# CW342_FPGIO_2.net
KiCad netlist of a schematic drawn in Altium Designer
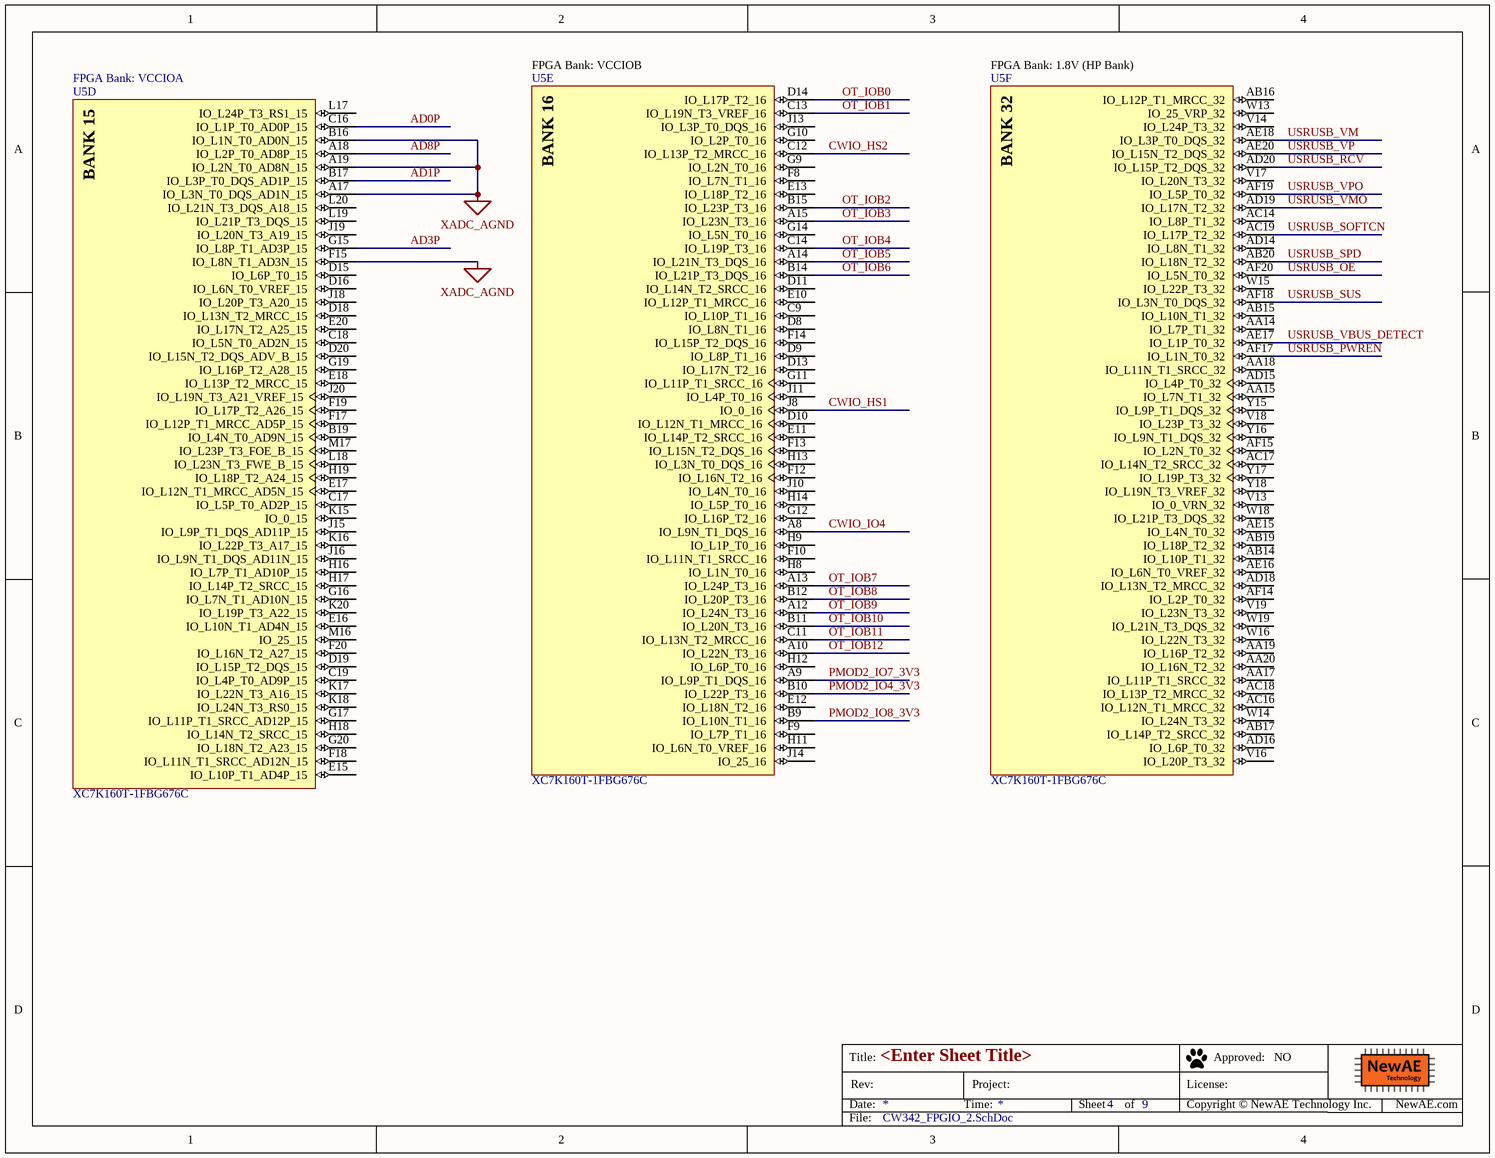
[diagram p0: CW342_FPGIO_2.SchDoc]

(export (version "E")
  (design (tool "Eeschema 10.0.6"))
  (components
    (comp (ref "U5")
      (value "XC7K160T-1FBG676C")
      (footprint "FBG676")
      (description "Kintex-7 FPGA, 400 User I/Os, 8 GTX, 676-Ball BGA, Speed Grade 1, Commercial Grade, Pb-Free")
      (fields (field (name "GENERIC PART NUMBER") "XC7K160T") (field (name "MANUFACTURER") "Xilinx"))
      (libsource (lib "") (part "XNLX-XC7K160T-XNLX-FBG676_1"))
    )
  )
  (nets
    (net (code "1") (name "/AD0P") (class "Default")
      (node (ref "U5") (pin "C16") (pinfunction "IO_L1P_T0_AD0P_15_C16") (pintype "bidirectional"))
    )
    (net (code "2") (name "/AD1P") (class "Default")
      (node (ref "U5") (pin "B17") (pinfunction "IO_L3P_T0_DQS_AD1P_15_B17") (pintype "bidirectional"))
    )
    (net (code "3") (name "/AD3P") (class "Default")
      (node (ref "U5") (pin "G15") (pinfunction "IO_L8P_T1_AD3P_15_G15") (pintype "bidirectional"))
    )
    (net (code "4") (name "/AD8P") (class "Default")
      (node (ref "U5") (pin "A18") (pinfunction "IO_L2P_T0_AD8P_15_A18") (pintype "bidirectional"))
    )
    (net (code "5") (name "/CWIO_HS1") (class "Default")
      (node (ref "U5") (pin "J8") (pinfunction "IO_0_16_J8") (pintype "bidirectional"))
    )
    (net (code "6") (name "/CWIO_HS2") (class "Default")
      (node (ref "U5") (pin "C12") (pinfunction "IO_L13P_T2_MRCC_16_C12") (pintype "bidirectional"))
    )
    (net (code "7") (name "/CWIO_IO4") (class "Default")
      (node (ref "U5") (pin "A8") (pinfunction "IO_L9N_T1_DQS_16_A8") (pintype "bidirectional"))
    )
    (net (code "8") (name "/OT_IOB0") (class "Default")
      (node (ref "U5") (pin "D14") (pinfunction "IO_L17P_T2_16_D14") (pintype "bidirectional"))
    )
    (net (code "9") (name "/OT_IOB1") (class "Default")
      (node (ref "U5") (pin "C13") (pinfunction "IO_L19N_T3_VREF_16_C13") (pintype "bidirectional"))
    )
    (net (code "10") (name "/OT_IOB2") (class "Default")
      (node (ref "U5") (pin "B15") (pinfunction "IO_L23P_T3_16_B15") (pintype "bidirectional"))
    )
    (net (code "11") (name "/OT_IOB3") (class "Default")
      (node (ref "U5") (pin "A15") (pinfunction "IO_L23N_T3_16_A15") (pintype "bidirectional"))
    )
    (net (code "12") (name "/OT_IOB4") (class "Default")
      (node (ref "U5") (pin "C14") (pinfunction "IO_L19P_T3_16_C14") (pintype "bidirectional"))
    )
    (net (code "13") (name "/OT_IOB5") (class "Default")
      (node (ref "U5") (pin "A14") (pinfunction "IO_L21N_T3_DQS_16_A14") (pintype "bidirectional"))
    )
    (net (code "14") (name "/OT_IOB6") (class "Default")
      (node (ref "U5") (pin "B14") (pinfunction "IO_L21P_T3_DQS_16_B14") (pintype "bidirectional"))
    )
    (net (code "15") (name "/OT_IOB7") (class "Default")
      (node (ref "U5") (pin "A13") (pinfunction "IO_L24P_T3_16_A13") (pintype "bidirectional"))
    )
    (net (code "16") (name "/OT_IOB8") (class "Default")
      (node (ref "U5") (pin "B12") (pinfunction "IO_L20P_T3_16_B12") (pintype "bidirectional"))
    )
    (net (code "17") (name "/OT_IOB9") (class "Default")
      (node (ref "U5") (pin "A12") (pinfunction "IO_L24N_T3_16_A12") (pintype "bidirectional"))
    )
    (net (code "18") (name "/OT_IOB10") (class "Default")
      (node (ref "U5") (pin "B11") (pinfunction "IO_L20N_T3_16_B11") (pintype "bidirectional"))
    )
    (net (code "19") (name "/OT_IOB11") (class "Default")
      (node (ref "U5") (pin "C11") (pinfunction "IO_L13N_T2_MRCC_16_C11") (pintype "bidirectional"))
    )
    (net (code "20") (name "/OT_IOB12") (class "Default")
      (node (ref "U5") (pin "A10") (pinfunction "IO_L22N_T3_16_A10") (pintype "bidirectional"))
    )
    (net (code "21") (name "/PMOD2_IO4_3V3") (class "Default")
      (node (ref "U5") (pin "B10") (pinfunction "IO_L22P_T3_16_B10") (pintype "bidirectional"))
    )
    (net (code "22") (name "/PMOD2_IO7_3V3") (class "Default")
      (node (ref "U5") (pin "A9") (pinfunction "IO_L9P_T1_DQS_16_A9") (pintype "bidirectional"))
    )
    (net (code "23") (name "/PMOD2_IO8_3V3") (class "Default")
      (node (ref "U5") (pin "B9") (pinfunction "IO_L10N_T1_16_B9") (pintype "bidirectional"))
    )
    (net (code "24") (name "/USRUSB_OE") (class "Default")
      (node (ref "U5") (pin "AF20") (pinfunction "IO_L5N_T0_32_AF20") (pintype "bidirectional"))
    )
    (net (code "25") (name "/USRUSB_PWREN") (class "Default")
      (node (ref "U5") (pin "AF17") (pinfunction "IO_L1N_T0_32_AF17") (pintype "bidirectional"))
    )
    (net (code "26") (name "/USRUSB_RCV") (class "Default")
      (node (ref "U5") (pin "AD20") (pinfunction "IO_L15P_T2_DQS_32_AD20") (pintype "bidirectional"))
    )
    (net (code "27") (name "/USRUSB_SOFTCN") (class "Default")
      (node (ref "U5") (pin "AC19") (pinfunction "IO_L17P_T2_32_AC19") (pintype "bidirectional"))
    )
    (net (code "28") (name "/USRUSB_SPD") (class "Default")
      (node (ref "U5") (pin "AB20") (pinfunction "IO_L18N_T2_32_AB20") (pintype "bidirectional"))
    )
    (net (code "29") (name "/USRUSB_SUS") (class "Default")
      (node (ref "U5") (pin "AF18") (pinfunction "IO_L3N_T0_DQS_32_AF18") (pintype "bidirectional"))
    )
    (net (code "30") (name "/USRUSB_VBUS_DETECT") (class "Default")
      (node (ref "U5") (pin "AE17") (pinfunction "IO_L1P_T0_32_AE17") (pintype "bidirectional"))
    )
    (net (code "31") (name "/USRUSB_VM") (class "Default")
      (node (ref "U5") (pin "AE18") (pinfunction "IO_L3P_T0_DQS_32_AE18") (pintype "bidirectional"))
    )
    (net (code "32") (name "/USRUSB_VMO") (class "Default")
      (node (ref "U5") (pin "AD19") (pinfunction "IO_L17N_T2_32_AD19") (pintype "bidirectional"))
    )
    (net (code "33") (name "/USRUSB_VP") (class "Default")
      (node (ref "U5") (pin "AE20") (pinfunction "IO_L15N_T2_DQS_32_AE20") (pintype "bidirectional"))
    )
    (net (code "34") (name "/USRUSB_VPO") (class "Default")
      (node (ref "U5") (pin "AF19") (pinfunction "IO_L5P_T0_32_AF19") (pintype "bidirectional"))
    )
    (net (code "35") (name "XADC_AGND") (class "Default")
      (node (ref "U5") (pin "A17") (pinfunction "IO_L3N_T0_DQS_AD1N_15_A17") (pintype "bidirectional"))
      (node (ref "U5") (pin "A19") (pinfunction "IO_L2N_T0_AD8N_15_A19") (pintype "bidirectional"))
      (node (ref "U5") (pin "B16") (pinfunction "IO_L1N_T0_AD0N_15_B16") (pintype "bidirectional"))
      (node (ref "U5") (pin "F15") (pinfunction "IO_L8N_T1_AD3N_15_F15") (pintype "bidirectional"))
    )
    (net (code "36") (name "unconnected-(U5D-IO_0_15-PadK15)") (class "Default")
      (node (ref "U5") (pin "K15") (pinfunction "IO_0_15_K15") (pintype "bidirectional"))
    )
    (net (code "37") (name "unconnected-(U5D-IO_25_15-PadM16)") (class "Default")
      (node (ref "U5") (pin "M16") (pinfunction "IO_25_15_M16") (pintype "bidirectional"))
    )
    (net (code "38") (name "unconnected-(U5D-IO_L4N_T0_AD9N_15-PadB19)") (class "Default")
      (node (ref "U5") (pin "B19") (pinfunction "IO_L4N_T0_AD9N_15_B19") (pintype "bidirectional"))
    )
    (net (code "39") (name "unconnected-(U5D-IO_L4P_T0_AD9P_15-PadC19)") (class "Default")
      (node (ref "U5") (pin "C19") (pinfunction "IO_L4P_T0_AD9P_15_C19") (pintype "bidirectional"))
    )
    (net (code "40") (name "unconnected-(U5D-IO_L5N_T0_AD2N_15-PadC18)") (class "Default")
      (node (ref "U5") (pin "C18") (pinfunction "IO_L5N_T0_AD2N_15_C18") (pintype "bidirectional"))
    )
    (net (code "41") (name "unconnected-(U5D-IO_L5P_T0_AD2P_15-PadC17)") (class "Default")
      (node (ref "U5") (pin "C17") (pinfunction "IO_L5P_T0_AD2P_15_C17") (pintype "bidirectional"))
    )
    (net (code "42") (name "unconnected-(U5D-IO_L6N_T0_VREF_15-PadD16)") (class "Default")
      (node (ref "U5") (pin "D16") (pinfunction "IO_L6N_T0_VREF_15_D16") (pintype "bidirectional"))
    )
    (net (code "43") (name "unconnected-(U5D-IO_L6P_T0_15-PadD15)") (class "Default")
      (node (ref "U5") (pin "D15") (pinfunction "IO_L6P_T0_15_D15") (pintype "bidirectional"))
    )
    (net (code "44") (name "unconnected-(U5D-IO_L7N_T1_AD10N_15-PadG16)") (class "Default")
      (node (ref "U5") (pin "G16") (pinfunction "IO_L7N_T1_AD10N_15_G16") (pintype "bidirectional"))
    )
    (net (code "45") (name "unconnected-(U5D-IO_L7P_T1_AD10P_15-PadH16)") (class "Default")
      (node (ref "U5") (pin "H16") (pinfunction "IO_L7P_T1_AD10P_15_H16") (pintype "bidirectional"))
    )
    (net (code "46") (name "unconnected-(U5D-IO_L9N_T1_DQS_AD11N_15-PadJ16)") (class "Default")
      (node (ref "U5") (pin "J16") (pinfunction "IO_L9N_T1_DQS_AD11N_15_J16") (pintype "bidirectional"))
    )
    (net (code "47") (name "unconnected-(U5D-IO_L9P_T1_DQS_AD11P_15-PadJ15)") (class "Default")
      (node (ref "U5") (pin "J15") (pinfunction "IO_L9P_T1_DQS_AD11P_15_J15") (pintype "bidirectional"))
    )
    (net (code "48") (name "unconnected-(U5D-IO_L10N_T1_AD4N_15-PadE16)") (class "Default")
      (node (ref "U5") (pin "E16") (pinfunction "IO_L10N_T1_AD4N_15_E16") (pintype "bidirectional"))
    )
    (net (code "49") (name "unconnected-(U5D-IO_L10P_T1_AD4P_15-PadE15)") (class "Default")
      (node (ref "U5") (pin "E15") (pinfunction "IO_L10P_T1_AD4P_15_E15") (pintype "bidirectional"))
    )
    (net (code "50") (name "unconnected-(U5D-IO_L11N_T1_SRCC_AD12N_15-PadF18)") (class "Default")
      (node (ref "U5") (pin "F18") (pinfunction "IO_L11N_T1_SRCC_AD12N_15_F18") (pintype "bidirectional"))
    )
    (net (code "51") (name "unconnected-(U5D-IO_L11P_T1_SRCC_AD12P_15-PadG17)") (class "Default")
      (node (ref "U5") (pin "G17") (pinfunction "IO_L11P_T1_SRCC_AD12P_15_G17") (pintype "bidirectional"))
    )
    (net (code "52") (name "unconnected-(U5D-IO_L12N_T1_MRCC_AD5N_15-PadE17)") (class "Default")
      (node (ref "U5") (pin "E17") (pinfunction "IO_L12N_T1_MRCC_AD5N_15_E17") (pintype "bidirectional"))
    )
    (net (code "53") (name "unconnected-(U5D-IO_L12P_T1_MRCC_AD5P_15-PadF17)") (class "Default")
      (node (ref "U5") (pin "F17") (pinfunction "IO_L12P_T1_MRCC_AD5P_15_F17") (pintype "bidirectional"))
    )
    (net (code "54") (name "unconnected-(U5D-IO_L13N_T2_MRCC_15-PadD18)") (class "Default")
      (node (ref "U5") (pin "D18") (pinfunction "IO_L13N_T2_MRCC_15_D18") (pintype "bidirectional"))
    )
    (net (code "55") (name "unconnected-(U5D-IO_L13P_T2_MRCC_15-PadE18)") (class "Default")
      (node (ref "U5") (pin "E18") (pinfunction "IO_L13P_T2_MRCC_15_E18") (pintype "bidirectional"))
    )
    (net (code "56") (name "unconnected-(U5D-IO_L14N_T2_SRCC_15-PadH18)") (class "Default")
      (node (ref "U5") (pin "H18") (pinfunction "IO_L14N_T2_SRCC_15_H18") (pintype "bidirectional"))
    )
    (net (code "57") (name "unconnected-(U5D-IO_L14P_T2_SRCC_15-PadH17)") (class "Default")
      (node (ref "U5") (pin "H17") (pinfunction "IO_L14P_T2_SRCC_15_H17") (pintype "bidirectional"))
    )
    (net (code "58") (name "unconnected-(U5D-IO_L15N_T2_DQS_ADV_B_15-PadD20)") (class "Default")
      (node (ref "U5") (pin "D20") (pinfunction "IO_L15N_T2_DQS_ADV_B_15_D20") (pintype "bidirectional"))
    )
    (net (code "59") (name "unconnected-(U5D-IO_L15P_T2_DQS_15-PadD19)") (class "Default")
      (node (ref "U5") (pin "D19") (pinfunction "IO_L15P_T2_DQS_15_D19") (pintype "bidirectional"))
    )
    (net (code "60") (name "unconnected-(U5D-IO_L16N_T2_A27_15-PadF20)") (class "Default")
      (node (ref "U5") (pin "F20") (pinfunction "IO_L16N_T2_A27_15_F20") (pintype "bidirectional"))
    )
    (net (code "61") (name "unconnected-(U5D-IO_L16P_T2_A28_15-PadG19)") (class "Default")
      (node (ref "U5") (pin "G19") (pinfunction "IO_L16P_T2_A28_15_G19") (pintype "bidirectional"))
    )
    (net (code "62") (name "unconnected-(U5D-IO_L17N_T2_A25_15-PadE20)") (class "Default")
      (node (ref "U5") (pin "E20") (pinfunction "IO_L17N_T2_A25_15_E20") (pintype "bidirectional"))
    )
    (net (code "63") (name "unconnected-(U5D-IO_L17P_T2_A26_15-PadF19)") (class "Default")
      (node (ref "U5") (pin "F19") (pinfunction "IO_L17P_T2_A26_15_F19") (pintype "bidirectional"))
    )
    (net (code "64") (name "unconnected-(U5D-IO_L18N_T2_A23_15-PadG20)") (class "Default")
      (node (ref "U5") (pin "G20") (pinfunction "IO_L18N_T2_A23_15_G20") (pintype "bidirectional"))
    )
    (net (code "65") (name "unconnected-(U5D-IO_L18P_T2_A24_15-PadH19)") (class "Default")
      (node (ref "U5") (pin "H19") (pinfunction "IO_L18P_T2_A24_15_H19") (pintype "bidirectional"))
    )
    (net (code "66") (name "unconnected-(U5D-IO_L19N_T3_A21_VREF_15-PadJ20)") (class "Default")
      (node (ref "U5") (pin "J20") (pinfunction "IO_L19N_T3_A21_VREF_15_J20") (pintype "bidirectional"))
    )
    (net (code "67") (name "unconnected-(U5D-IO_L19P_T3_A22_15-PadK20)") (class "Default")
      (node (ref "U5") (pin "K20") (pinfunction "IO_L19P_T3_A22_15_K20") (pintype "bidirectional"))
    )
    (net (code "68") (name "unconnected-(U5D-IO_L20N_T3_A19_15-PadJ19)") (class "Default")
      (node (ref "U5") (pin "J19") (pinfunction "IO_L20N_T3_A19_15_J19") (pintype "bidirectional"))
    )
    (net (code "69") (name "unconnected-(U5D-IO_L20P_T3_A20_15-PadJ18)") (class "Default")
      (node (ref "U5") (pin "J18") (pinfunction "IO_L20P_T3_A20_15_J18") (pintype "bidirectional"))
    )
    (net (code "70") (name "unconnected-(U5D-IO_L21N_T3_DQS_A18_15-PadL20)") (class "Default")
      (node (ref "U5") (pin "L20") (pinfunction "IO_L21N_T3_DQS_A18_15_L20") (pintype "bidirectional"))
    )
    (net (code "71") (name "unconnected-(U5D-IO_L21P_T3_DQS_15-PadL19)") (class "Default")
      (node (ref "U5") (pin "L19") (pinfunction "IO_L21P_T3_DQS_15_L19") (pintype "bidirectional"))
    )
    (net (code "72") (name "unconnected-(U5D-IO_L22N_T3_A16_15-PadK17)") (class "Default")
      (node (ref "U5") (pin "K17") (pinfunction "IO_L22N_T3_A16_15_K17") (pintype "bidirectional"))
    )
    (net (code "73") (name "unconnected-(U5D-IO_L22P_T3_A17_15-PadK16)") (class "Default")
      (node (ref "U5") (pin "K16") (pinfunction "IO_L22P_T3_A17_15_K16") (pintype "bidirectional"))
    )
    (net (code "74") (name "unconnected-(U5D-IO_L23N_T3_FWE_B_15-PadL18)") (class "Default")
      (node (ref "U5") (pin "L18") (pinfunction "IO_L23N_T3_FWE_B_15_L18") (pintype "bidirectional"))
    )
    (net (code "75") (name "unconnected-(U5D-IO_L23P_T3_FOE_B_15-PadM17)") (class "Default")
      (node (ref "U5") (pin "M17") (pinfunction "IO_L23P_T3_FOE_B_15_M17") (pintype "bidirectional"))
    )
    (net (code "76") (name "unconnected-(U5D-IO_L24N_T3_RS0_15-PadK18)") (class "Default")
      (node (ref "U5") (pin "K18") (pinfunction "IO_L24N_T3_RS0_15_K18") (pintype "bidirectional"))
    )
    (net (code "77") (name "unconnected-(U5D-IO_L24P_T3_RS1_15-PadL17)") (class "Default")
      (node (ref "U5") (pin "L17") (pinfunction "IO_L24P_T3_RS1_15_L17") (pintype "bidirectional"))
    )
    (net (code "78") (name "unconnected-(U5E-IO_25_16-PadJ14)") (class "Default")
      (node (ref "U5") (pin "J14") (pinfunction "IO_25_16_J14") (pintype "bidirectional"))
    )
    (net (code "79") (name "unconnected-(U5E-IO_L1N_T0_16-PadH8)") (class "Default")
      (node (ref "U5") (pin "H8") (pinfunction "IO_L1N_T0_16_H8") (pintype "bidirectional"))
    )
    (net (code "80") (name "unconnected-(U5E-IO_L1P_T0_16-PadH9)") (class "Default")
      (node (ref "U5") (pin "H9") (pinfunction "IO_L1P_T0_16_H9") (pintype "bidirectional"))
    )
    (net (code "81") (name "unconnected-(U5E-IO_L2N_T0_16-PadG9)") (class "Default")
      (node (ref "U5") (pin "G9") (pinfunction "IO_L2N_T0_16_G9") (pintype "bidirectional"))
    )
    (net (code "82") (name "unconnected-(U5E-IO_L2P_T0_16-PadG10)") (class "Default")
      (node (ref "U5") (pin "G10") (pinfunction "IO_L2P_T0_16_G10") (pintype "bidirectional"))
    )
    (net (code "83") (name "unconnected-(U5E-IO_L3N_T0_DQS_16-PadH13)") (class "Default")
      (node (ref "U5") (pin "H13") (pinfunction "IO_L3N_T0_DQS_16_H13") (pintype "bidirectional"))
    )
    (net (code "84") (name "unconnected-(U5E-IO_L3P_T0_DQS_16-PadJ13)") (class "Default")
      (node (ref "U5") (pin "J13") (pinfunction "IO_L3P_T0_DQS_16_J13") (pintype "bidirectional"))
    )
    (net (code "85") (name "unconnected-(U5E-IO_L4N_T0_16-PadJ10)") (class "Default")
      (node (ref "U5") (pin "J10") (pinfunction "IO_L4N_T0_16_J10") (pintype "bidirectional"))
    )
    (net (code "86") (name "unconnected-(U5E-IO_L4P_T0_16-PadJ11)") (class "Default")
      (node (ref "U5") (pin "J11") (pinfunction "IO_L4P_T0_16_J11") (pintype "bidirectional"))
    )
    (net (code "87") (name "unconnected-(U5E-IO_L5N_T0_16-PadG14)") (class "Default")
      (node (ref "U5") (pin "G14") (pinfunction "IO_L5N_T0_16_G14") (pintype "bidirectional"))
    )
    (net (code "88") (name "unconnected-(U5E-IO_L5P_T0_16-PadH14)") (class "Default")
      (node (ref "U5") (pin "H14") (pinfunction "IO_L5P_T0_16_H14") (pintype "bidirectional"))
    )
    (net (code "89") (name "unconnected-(U5E-IO_L6N_T0_VREF_16-PadH11)") (class "Default")
      (node (ref "U5") (pin "H11") (pinfunction "IO_L6N_T0_VREF_16_H11") (pintype "bidirectional"))
    )
    (net (code "90") (name "unconnected-(U5E-IO_L6P_T0_16-PadH12)") (class "Default")
      (node (ref "U5") (pin "H12") (pinfunction "IO_L6P_T0_16_H12") (pintype "bidirectional"))
    )
    (net (code "91") (name "unconnected-(U5E-IO_L7N_T1_16-PadF8)") (class "Default")
      (node (ref "U5") (pin "F8") (pinfunction "IO_L7N_T1_16_F8") (pintype "bidirectional"))
    )
    (net (code "92") (name "unconnected-(U5E-IO_L7P_T1_16-PadF9)") (class "Default")
      (node (ref "U5") (pin "F9") (pinfunction "IO_L7P_T1_16_F9") (pintype "bidirectional"))
    )
    (net (code "93") (name "unconnected-(U5E-IO_L8N_T1_16-PadD8)") (class "Default")
      (node (ref "U5") (pin "D8") (pinfunction "IO_L8N_T1_16_D8") (pintype "bidirectional"))
    )
    (net (code "94") (name "unconnected-(U5E-IO_L8P_T1_16-PadD9)") (class "Default")
      (node (ref "U5") (pin "D9") (pinfunction "IO_L8P_T1_16_D9") (pintype "bidirectional"))
    )
    (net (code "95") (name "unconnected-(U5E-IO_L10P_T1_16-PadC9)") (class "Default")
      (node (ref "U5") (pin "C9") (pinfunction "IO_L10P_T1_16_C9") (pintype "bidirectional"))
    )
    (net (code "96") (name "unconnected-(U5E-IO_L11N_T1_SRCC_16-PadF10)") (class "Default")
      (node (ref "U5") (pin "F10") (pinfunction "IO_L11N_T1_SRCC_16_F10") (pintype "bidirectional"))
    )
    (net (code "97") (name "unconnected-(U5E-IO_L11P_T1_SRCC_16-PadG11)") (class "Default")
      (node (ref "U5") (pin "G11") (pinfunction "IO_L11P_T1_SRCC_16_G11") (pintype "bidirectional"))
    )
    (net (code "98") (name "unconnected-(U5E-IO_L12N_T1_MRCC_16-PadD10)") (class "Default")
      (node (ref "U5") (pin "D10") (pinfunction "IO_L12N_T1_MRCC_16_D10") (pintype "bidirectional"))
    )
    (net (code "99") (name "unconnected-(U5E-IO_L12P_T1_MRCC_16-PadE10)") (class "Default")
      (node (ref "U5") (pin "E10") (pinfunction "IO_L12P_T1_MRCC_16_E10") (pintype "bidirectional"))
    )
    (net (code "100") (name "unconnected-(U5E-IO_L14N_T2_SRCC_16-PadD11)") (class "Default")
      (node (ref "U5") (pin "D11") (pinfunction "IO_L14N_T2_SRCC_16_D11") (pintype "bidirectional"))
    )
    (net (code "101") (name "unconnected-(U5E-IO_L14P_T2_SRCC_16-PadE11)") (class "Default")
      (node (ref "U5") (pin "E11") (pinfunction "IO_L14P_T2_SRCC_16_E11") (pintype "bidirectional"))
    )
    (net (code "102") (name "unconnected-(U5E-IO_L15N_T2_DQS_16-PadF13)") (class "Default")
      (node (ref "U5") (pin "F13") (pinfunction "IO_L15N_T2_DQS_16_F13") (pintype "bidirectional"))
    )
    (net (code "103") (name "unconnected-(U5E-IO_L15P_T2_DQS_16-PadF14)") (class "Default")
      (node (ref "U5") (pin "F14") (pinfunction "IO_L15P_T2_DQS_16_F14") (pintype "bidirectional"))
    )
    (net (code "104") (name "unconnected-(U5E-IO_L16N_T2_16-PadF12)") (class "Default")
      (node (ref "U5") (pin "F12") (pinfunction "IO_L16N_T2_16_F12") (pintype "bidirectional"))
    )
    (net (code "105") (name "unconnected-(U5E-IO_L16P_T2_16-PadG12)") (class "Default")
      (node (ref "U5") (pin "G12") (pinfunction "IO_L16P_T2_16_G12") (pintype "bidirectional"))
    )
    (net (code "106") (name "unconnected-(U5E-IO_L17N_T2_16-PadD13)") (class "Default")
      (node (ref "U5") (pin "D13") (pinfunction "IO_L17N_T2_16_D13") (pintype "bidirectional"))
    )
    (net (code "107") (name "unconnected-(U5E-IO_L18N_T2_16-PadE12)") (class "Default")
      (node (ref "U5") (pin "E12") (pinfunction "IO_L18N_T2_16_E12") (pintype "bidirectional"))
    )
    (net (code "108") (name "unconnected-(U5E-IO_L18P_T2_16-PadE13)") (class "Default")
      (node (ref "U5") (pin "E13") (pinfunction "IO_L18P_T2_16_E13") (pintype "bidirectional"))
    )
    (net (code "109") (name "unconnected-(U5F-IO_0_VRN_32-PadV13)") (class "Default")
      (node (ref "U5") (pin "V13") (pinfunction "IO_0_VRN_32_V13") (pintype "bidirectional"))
    )
    (net (code "110") (name "unconnected-(U5F-IO_25_VRP_32-PadW13)") (class "Default")
      (node (ref "U5") (pin "W13") (pinfunction "IO_25_VRP_32_W13") (pintype "bidirectional"))
    )
    (net (code "111") (name "unconnected-(U5F-IO_L2N_T0_32-PadAF15)") (class "Default")
      (node (ref "U5") (pin "AF15") (pinfunction "IO_L2N_T0_32_AF15") (pintype "bidirectional"))
    )
    (net (code "112") (name "unconnected-(U5F-IO_L2P_T0_32-PadAF14)") (class "Default")
      (node (ref "U5") (pin "AF14") (pinfunction "IO_L2P_T0_32_AF14") (pintype "bidirectional"))
    )
    (net (code "113") (name "unconnected-(U5F-IO_L4N_T0_32-PadAE15)") (class "Default")
      (node (ref "U5") (pin "AE15") (pinfunction "IO_L4N_T0_32_AE15") (pintype "bidirectional"))
    )
    (net (code "114") (name "unconnected-(U5F-IO_L4P_T0_32-PadAD15)") (class "Default")
      (node (ref "U5") (pin "AD15") (pinfunction "IO_L4P_T0_32_AD15") (pintype "bidirectional"))
    )
    (net (code "115") (name "unconnected-(U5F-IO_L6N_T0_VREF_32-PadAE16)") (class "Default")
      (node (ref "U5") (pin "AE16") (pinfunction "IO_L6N_T0_VREF_32_AE16") (pintype "bidirectional"))
    )
    (net (code "116") (name "unconnected-(U5F-IO_L6P_T0_32-PadAD16)") (class "Default")
      (node (ref "U5") (pin "AD16") (pinfunction "IO_L6P_T0_32_AD16") (pintype "bidirectional"))
    )
    (net (code "117") (name "unconnected-(U5F-IO_L7N_T1_32-PadAA15)") (class "Default")
      (node (ref "U5") (pin "AA15") (pinfunction "IO_L7N_T1_32_AA15") (pintype "bidirectional"))
    )
    (net (code "118") (name "unconnected-(U5F-IO_L7P_T1_32-PadAA14)") (class "Default")
      (node (ref "U5") (pin "AA14") (pinfunction "IO_L7P_T1_32_AA14") (pintype "bidirectional"))
    )
    (net (code "119") (name "unconnected-(U5F-IO_L8N_T1_32-PadAD14)") (class "Default")
      (node (ref "U5") (pin "AD14") (pinfunction "IO_L8N_T1_32_AD14") (pintype "bidirectional"))
    )
    (net (code "120") (name "unconnected-(U5F-IO_L8P_T1_32-PadAC14)") (class "Default")
      (node (ref "U5") (pin "AC14") (pinfunction "IO_L8P_T1_32_AC14") (pintype "bidirectional"))
    )
    (net (code "121") (name "unconnected-(U5F-IO_L9N_T1_DQS_32-PadY16)") (class "Default")
      (node (ref "U5") (pin "Y16") (pinfunction "IO_L9N_T1_DQS_32_Y16") (pintype "bidirectional"))
    )
    (net (code "122") (name "unconnected-(U5F-IO_L9P_T1_DQS_32-PadY15)") (class "Default")
      (node (ref "U5") (pin "Y15") (pinfunction "IO_L9P_T1_DQS_32_Y15") (pintype "bidirectional"))
    )
    (net (code "123") (name "unconnected-(U5F-IO_L10N_T1_32-PadAB15)") (class "Default")
      (node (ref "U5") (pin "AB15") (pinfunction "IO_L10N_T1_32_AB15") (pintype "bidirectional"))
    )
    (net (code "124") (name "unconnected-(U5F-IO_L10P_T1_32-PadAB14)") (class "Default")
      (node (ref "U5") (pin "AB14") (pinfunction "IO_L10P_T1_32_AB14") (pintype "bidirectional"))
    )
    (net (code "125") (name "unconnected-(U5F-IO_L11N_T1_SRCC_32-PadAA18)") (class "Default")
      (node (ref "U5") (pin "AA18") (pinfunction "IO_L11N_T1_SRCC_32_AA18") (pintype "bidirectional"))
    )
    (net (code "126") (name "unconnected-(U5F-IO_L11P_T1_SRCC_32-PadAA17)") (class "Default")
      (node (ref "U5") (pin "AA17") (pinfunction "IO_L11P_T1_SRCC_32_AA17") (pintype "bidirectional"))
    )
    (net (code "127") (name "unconnected-(U5F-IO_L12N_T1_MRCC_32-PadAC16)") (class "Default")
      (node (ref "U5") (pin "AC16") (pinfunction "IO_L12N_T1_MRCC_32_AC16") (pintype "bidirectional"))
    )
    (net (code "128") (name "unconnected-(U5F-IO_L12P_T1_MRCC_32-PadAB16)") (class "Default")
      (node (ref "U5") (pin "AB16") (pinfunction "IO_L12P_T1_MRCC_32_AB16") (pintype "bidirectional"))
    )
    (net (code "129") (name "unconnected-(U5F-IO_L13N_T2_MRCC_32-PadAD18)") (class "Default")
      (node (ref "U5") (pin "AD18") (pinfunction "IO_L13N_T2_MRCC_32_AD18") (pintype "bidirectional"))
    )
    (net (code "130") (name "unconnected-(U5F-IO_L13P_T2_MRCC_32-PadAC18)") (class "Default")
      (node (ref "U5") (pin "AC18") (pinfunction "IO_L13P_T2_MRCC_32_AC18") (pintype "bidirectional"))
    )
    (net (code "131") (name "unconnected-(U5F-IO_L14N_T2_SRCC_32-PadAC17)") (class "Default")
      (node (ref "U5") (pin "AC17") (pinfunction "IO_L14N_T2_SRCC_32_AC17") (pintype "bidirectional"))
    )
    (net (code "132") (name "unconnected-(U5F-IO_L14P_T2_SRCC_32-PadAB17)") (class "Default")
      (node (ref "U5") (pin "AB17") (pinfunction "IO_L14P_T2_SRCC_32_AB17") (pintype "bidirectional"))
    )
    (net (code "133") (name "unconnected-(U5F-IO_L16N_T2_32-PadAA20)") (class "Default")
      (node (ref "U5") (pin "AA20") (pinfunction "IO_L16N_T2_32_AA20") (pintype "bidirectional"))
    )
    (net (code "134") (name "unconnected-(U5F-IO_L16P_T2_32-PadAA19)") (class "Default")
      (node (ref "U5") (pin "AA19") (pinfunction "IO_L16P_T2_32_AA19") (pintype "bidirectional"))
    )
    (net (code "135") (name "unconnected-(U5F-IO_L18P_T2_32-PadAB19)") (class "Default")
      (node (ref "U5") (pin "AB19") (pinfunction "IO_L18P_T2_32_AB19") (pintype "bidirectional"))
    )
    (net (code "136") (name "unconnected-(U5F-IO_L19N_T3_VREF_32-PadY18)") (class "Default")
      (node (ref "U5") (pin "Y18") (pinfunction "IO_L19N_T3_VREF_32_Y18") (pintype "bidirectional"))
    )
    (net (code "137") (name "unconnected-(U5F-IO_L19P_T3_32-PadY17)") (class "Default")
      (node (ref "U5") (pin "Y17") (pinfunction "IO_L19P_T3_32_Y17") (pintype "bidirectional"))
    )
    (net (code "138") (name "unconnected-(U5F-IO_L20N_T3_32-PadV17)") (class "Default")
      (node (ref "U5") (pin "V17") (pinfunction "IO_L20N_T3_32_V17") (pintype "bidirectional"))
    )
    (net (code "139") (name "unconnected-(U5F-IO_L20P_T3_32-PadV16)") (class "Default")
      (node (ref "U5") (pin "V16") (pinfunction "IO_L20P_T3_32_V16") (pintype "bidirectional"))
    )
    (net (code "140") (name "unconnected-(U5F-IO_L21N_T3_DQS_32-PadW19)") (class "Default")
      (node (ref "U5") (pin "W19") (pinfunction "IO_L21N_T3_DQS_32_W19") (pintype "bidirectional"))
    )
    (net (code "141") (name "unconnected-(U5F-IO_L21P_T3_DQS_32-PadW18)") (class "Default")
      (node (ref "U5") (pin "W18") (pinfunction "IO_L21P_T3_DQS_32_W18") (pintype "bidirectional"))
    )
    (net (code "142") (name "unconnected-(U5F-IO_L22N_T3_32-PadW16)") (class "Default")
      (node (ref "U5") (pin "W16") (pinfunction "IO_L22N_T3_32_W16") (pintype "bidirectional"))
    )
    (net (code "143") (name "unconnected-(U5F-IO_L22P_T3_32-PadW15)") (class "Default")
      (node (ref "U5") (pin "W15") (pinfunction "IO_L22P_T3_32_W15") (pintype "bidirectional"))
    )
    (net (code "144") (name "unconnected-(U5F-IO_L23N_T3_32-PadV19)") (class "Default")
      (node (ref "U5") (pin "V19") (pinfunction "IO_L23N_T3_32_V19") (pintype "bidirectional"))
    )
    (net (code "145") (name "unconnected-(U5F-IO_L23P_T3_32-PadV18)") (class "Default")
      (node (ref "U5") (pin "V18") (pinfunction "IO_L23P_T3_32_V18") (pintype "bidirectional"))
    )
    (net (code "146") (name "unconnected-(U5F-IO_L24N_T3_32-PadW14)") (class "Default")
      (node (ref "U5") (pin "W14") (pinfunction "IO_L24N_T3_32_W14") (pintype "bidirectional"))
    )
    (net (code "147") (name "unconnected-(U5F-IO_L24P_T3_32-PadV14)") (class "Default")
      (node (ref "U5") (pin "V14") (pinfunction "IO_L24P_T3_32_V14") (pintype "bidirectional"))
    )
  )
)
